# Part13_Power.net
KiCad netlist of a schematic drawn in Altium Designer
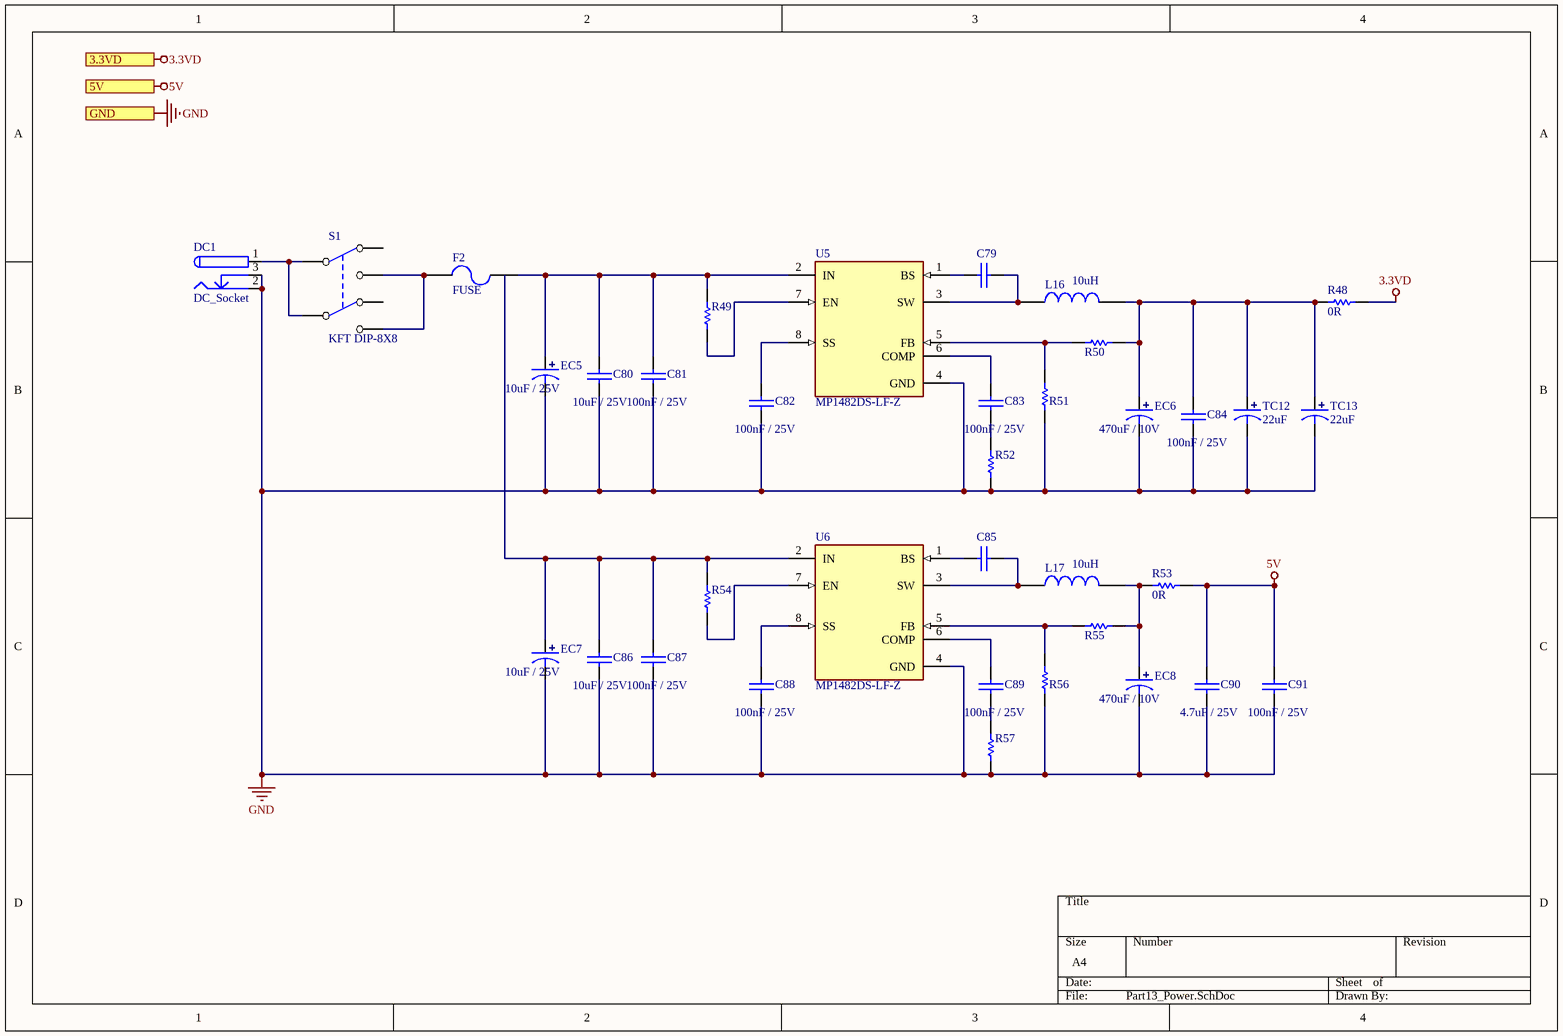
[diagram p0: Part13_Power.SchDoc]

(export (version "E")
  (design (tool "Eeschema 10.0.6"))
  (components
    (comp (ref "C79")
      (value "10nF / 25V")
      (footprint "0603C")
      (description "无极性电容")
      (libsource (lib "电容") (part "CAP"))
    )
    (comp (ref "C80")
      (value "10uF / 25V")
      (footprint "0603C")
      (description "无极性电容")
      (libsource (lib "电容") (part "CAP"))
    )
    (comp (ref "C81")
      (value "100nF / 25V")
      (footprint "0603C")
      (description "无极性电容")
      (libsource (lib "电容") (part "CAP"))
    )
    (comp (ref "C82")
      (value "100nF / 25V")
      (footprint "0603C")
      (description "无极性电容")
      (libsource (lib "电容") (part "CAP"))
    )
    (comp (ref "C83")
      (value "100nF / 25V")
      (footprint "0603C")
      (description "无极性电容")
      (libsource (lib "电容") (part "CAP"))
    )
    (comp (ref "C84")
      (value "100nF / 25V")
      (footprint "0603C")
      (description "无极性电容")
      (libsource (lib "电容") (part "CAP"))
    )
    (comp (ref "C85")
      (value "10nF / 25V")
      (footprint "0603C")
      (description "无极性电容")
      (libsource (lib "电容") (part "CAP"))
    )
    (comp (ref "C86")
      (value "10uF / 25V")
      (footprint "0603C")
      (description "无极性电容")
      (libsource (lib "电容") (part "CAP"))
    )
    (comp (ref "C87")
      (value "100nF / 25V")
      (footprint "0603C")
      (description "无极性电容")
      (libsource (lib "电容") (part "CAP"))
    )
    (comp (ref "C88")
      (value "100nF / 25V")
      (footprint "0603C")
      (description "无极性电容")
      (libsource (lib "电容") (part "CAP"))
    )
    (comp (ref "C89")
      (value "100nF / 25V")
      (footprint "0603C")
      (description "无极性电容")
      (libsource (lib "电容") (part "CAP"))
    )
    (comp (ref "C90")
      (value "4.7uF / 25V")
      (footprint "0603C")
      (description "无极性电容")
      (libsource (lib "电容") (part "CAP"))
    )
    (comp (ref "C91")
      (value "100nF / 25V")
      (footprint "0603C")
      (description "无极性电容")
      (libsource (lib "电容") (part "CAP"))
    )
    (comp (ref "DC1") (value "DC_Socket") (footprint "DC-005") (libsource (lib "电源插座") (part "DC_Socket")))
    (comp (ref "EC5")
      (value "10uF / 25V")
      (footprint "SMD-EC4.0X4.3X5.4")
      (description "贴片电解电容")
      (libsource (lib "电容") (part "SMD_ECAP"))
    )
    (comp (ref "EC6")
      (value "470uF / 10V")
      (footprint "SMD-EC6.3X6.3X10")
      (description "贴片电解电容")
      (libsource (lib "电容") (part "SMD_ECAP"))
    )
    (comp (ref "EC7")
      (value "10uF / 25V")
      (footprint "SMD-EC4.0X4.3X5.4")
      (description "贴片电解电容")
      (libsource (lib "电容") (part "SMD_ECAP"))
    )
    (comp (ref "EC8")
      (value "470uF / 10V")
      (footprint "SMD-EC6.3X6.3X10")
      (description "贴片电解电容")
      (libsource (lib "电容") (part "SMD_ECAP"))
    )
    (comp (ref "F2") (value "FUSE") (footprint "FUSE-1210") (libsource (lib "保险丝") (part "FUSE")))
    (comp (ref "L16")
      (value "10uH")
      (footprint "CD42")
      (description "INDUCTOR")
      (libsource (lib "电感") (part "INDUCTOR"))
    )
    (comp (ref "L17")
      (value "10uH")
      (footprint "CD42")
      (description "INDUCTOR")
      (libsource (lib "电感") (part "INDUCTOR"))
    )
    (comp (ref "R48") (value "0R") (footprint "0603R") (libsource (lib "电阻") (part "RES")))
    (comp (ref "R49") (value "30K") (footprint "0402R") (libsource (lib "电阻") (part "RES")))
    (comp (ref "R50") (value "26.1k / 1%") (footprint "0402R") (libsource (lib "电阻") (part "RES")))
    (comp (ref "R51") (value "10K / 1%") (footprint "0402R") (libsource (lib "电阻") (part "RES")))
    (comp (ref "R52") (value "5.6k") (footprint "0402R") (libsource (lib "电阻") (part "RES")))
    (comp (ref "R53") (value "0R") (footprint "0603R") (libsource (lib "电阻") (part "RES")))
    (comp (ref "R54") (value "30K") (footprint "0402R") (libsource (lib "电阻") (part "RES")))
    (comp (ref "R55") (value "26.1k / 1%") (footprint "0402R") (libsource (lib "电阻") (part "RES")))
    (comp (ref "R56") (value "10K / 1%") (footprint "0402R") (libsource (lib "电阻") (part "RES")))
    (comp (ref "R57") (value "5.6k") (footprint "0402R") (libsource (lib "电阻") (part "RES")))
    (comp (ref "S1")
      (value "KFT DIP-8X8")
      (footprint "KFT DIP-8X8")
      (libsource (lib "电源开关") (part "KFT DIP-8X8"))
    )
    (comp (ref "TC12")
      (value "22uF")
      (footprint "TAJ-A/3216")
      (description "钽电容")
      (libsource (lib "电容") (part "TCAP"))
    )
    (comp (ref "TC13")
      (value "22uF")
      (footprint "TAJ-A/3216")
      (description "钽电容")
      (libsource (lib "电容") (part "TCAP"))
    )
    (comp (ref "U5")
      (value "MP1482DS-LF-Z")
      (footprint "FP-MP1482DS-LF-Z-MFG")
      (description "IC REG BUCK ADJUSTABLE 2A 8SOIC")
      (fields
        (field (name "MANUFACTURER") "Monolithic Power Systems")
        (field (name "OCTOPART") "https://octopart.com/mp1482ds-lf-z-monolithic+power+systems-17392490")
      )
      (libsource (lib "Altium Content Vault") (part "ebfa2809f2b7d2844d3c4bd6b7ab285"))
    )
    (comp (ref "U6")
      (value "MP1482DS-LF-Z")
      (footprint "FP-MP1482DS-LF-Z-MFG")
      (description "IC REG BUCK ADJUSTABLE 2A 8SOIC")
      (fields
        (field (name "MANUFACTURER") "Monolithic Power Systems")
        (field (name "OCTOPART") "https://octopart.com/mp1482ds-lf-z-monolithic+power+systems-17392490")
      )
      (libsource (lib "Altium Content Vault") (part "ebfa2809f2b7d2844d3c4bd6b7ab285"))
    )
  )
  (nets
    (net (code "1") (name "3.3VD") (class "Default")
      (node (ref "R48") (pin "2") (pinfunction "2_2") (pintype "passive"))
    )
    (net (code "2") (name "5V") (class "Default")
      (node (ref "C90") (pin "2") (pinfunction "2_2") (pintype "passive"))
      (node (ref "C91") (pin "2") (pinfunction "2_2") (pintype "passive"))
      (node (ref "R53") (pin "2") (pinfunction "2_2") (pintype "passive"))
    )
    (net (code "3") (name "GND") (class "Default")
      (node (ref "C80") (pin "1") (pinfunction "1_1") (pintype "passive"))
      (node (ref "C81") (pin "1") (pinfunction "1_1") (pintype "passive"))
      (node (ref "C82") (pin "1") (pinfunction "1_1") (pintype "passive"))
      (node (ref "C84") (pin "1") (pinfunction "1_1") (pintype "passive"))
      (node (ref "C86") (pin "1") (pinfunction "1_1") (pintype "passive"))
      (node (ref "C87") (pin "1") (pinfunction "1_1") (pintype "passive"))
      (node (ref "C88") (pin "1") (pinfunction "1_1") (pintype "passive"))
      (node (ref "C90") (pin "1") (pinfunction "1_1") (pintype "passive"))
      (node (ref "C91") (pin "1") (pinfunction "1_1") (pintype "passive"))
      (node (ref "DC1") (pin "2") (pinfunction "2_2") (pintype "power_in"))
      (node (ref "DC1") (pin "3") (pinfunction "3_3") (pintype "power_in"))
      (node (ref "EC5") (pin "2") (pinfunction "2_2") (pintype "passive"))
      (node (ref "EC6") (pin "2") (pinfunction "2_2") (pintype "passive"))
      (node (ref "EC7") (pin "2") (pinfunction "2_2") (pintype "passive"))
      (node (ref "EC8") (pin "2") (pinfunction "2_2") (pintype "passive"))
      (node (ref "R51") (pin "1") (pinfunction "1_1") (pintype "passive"))
      (node (ref "R52") (pin "2") (pinfunction "2_2") (pintype "passive"))
      (node (ref "R56") (pin "1") (pinfunction "1_1") (pintype "passive"))
      (node (ref "R57") (pin "2") (pinfunction "2_2") (pintype "passive"))
      (node (ref "TC12") (pin "2") (pinfunction "2_2") (pintype "passive"))
      (node (ref "TC13") (pin "2") (pinfunction "2_2") (pintype "passive"))
      (node (ref "U5") (pin "4") (pinfunction "GND_4") (pintype "power_in"))
      (node (ref "U6") (pin "4") (pinfunction "GND_4") (pintype "power_in"))
    )
    (net (code "4") (name "Net-(C83-Pad1)") (class "Default")
      (node (ref "C83") (pin "1") (pinfunction "1_1") (pintype "passive"))
      (node (ref "R52") (pin "1") (pinfunction "1_1") (pintype "passive"))
    )
    (net (code "5") (name "Net-(C84-Pad2)") (class "Default")
      (node (ref "C84") (pin "2") (pinfunction "2_2") (pintype "passive"))
      (node (ref "EC6") (pin "1") (pinfunction "1_1") (pintype "passive"))
      (node (ref "L16") (pin "2") (pinfunction "2_2") (pintype "passive"))
      (node (ref "R48") (pin "1") (pinfunction "1_1") (pintype "passive"))
      (node (ref "R50") (pin "2") (pinfunction "2_2") (pintype "passive"))
      (node (ref "TC12") (pin "1") (pinfunction "1_1") (pintype "passive"))
      (node (ref "TC13") (pin "1") (pinfunction "1_1") (pintype "passive"))
    )
    (net (code "6") (name "Net-(C89-Pad1)") (class "Default")
      (node (ref "C89") (pin "1") (pinfunction "1_1") (pintype "passive"))
      (node (ref "R57") (pin "1") (pinfunction "1_1") (pintype "passive"))
    )
    (net (code "7") (name "Net-(DC1-Pad1)") (class "Default")
      (node (ref "DC1") (pin "1") (pinfunction "1_1") (pintype "power_in"))
      (node (ref "S1") (pin "2") (pinfunction "2_2") (pintype "passive"))
      (node (ref "S1") (pin "5") (pinfunction "5_5") (pintype "passive"))
    )
    (net (code "8") (name "Net-(EC8-Pad1)") (class "Default")
      (node (ref "EC8") (pin "1") (pinfunction "1_1") (pintype "passive"))
      (node (ref "L17") (pin "2") (pinfunction "2_2") (pintype "passive"))
      (node (ref "R53") (pin "1") (pinfunction "1_1") (pintype "passive"))
      (node (ref "R55") (pin "2") (pinfunction "2_2") (pintype "passive"))
    )
    (net (code "9") (name "Net-(F2-Pad1)") (class "Default")
      (node (ref "F2") (pin "1") (pinfunction "1_1") (pintype "passive"))
      (node (ref "S1") (pin "1") (pinfunction "1_1") (pintype "passive"))
      (node (ref "S1") (pin "6") (pinfunction "6_6") (pintype "passive"))
    )
    (net (code "10") (name "Net-(U5-BS)") (class "Default")
      (node (ref "C79") (pin "2") (pinfunction "2_2") (pintype "passive"))
      (node (ref "U5") (pin "1") (pinfunction "BS_1") (pintype "input"))
    )
    (net (code "11") (name "Net-(U5-COMP)") (class "Default")
      (node (ref "C83") (pin "2") (pinfunction "2_2") (pintype "passive"))
      (node (ref "U5") (pin "6") (pinfunction "COMP_6") (pintype "passive"))
    )
    (net (code "12") (name "Net-(U5-EN)") (class "Default")
      (node (ref "R49") (pin "2") (pinfunction "2_2") (pintype "passive"))
      (node (ref "U5") (pin "7") (pinfunction "EN_7") (pintype "input"))
    )
    (net (code "13") (name "Net-(U5-FB)") (class "Default")
      (node (ref "R50") (pin "1") (pinfunction "1_1") (pintype "passive"))
      (node (ref "R51") (pin "2") (pinfunction "2_2") (pintype "passive"))
      (node (ref "U5") (pin "5") (pinfunction "FB_5") (pintype "input"))
    )
    (net (code "14") (name "Net-(U5-IN)") (class "Default")
      (node (ref "C80") (pin "2") (pinfunction "2_2") (pintype "passive"))
      (node (ref "C81") (pin "2") (pinfunction "2_2") (pintype "passive"))
      (node (ref "EC5") (pin "1") (pinfunction "1_1") (pintype "passive"))
      (node (ref "F2") (pin "2") (pinfunction "2_2") (pintype "passive"))
      (node (ref "R49") (pin "1") (pinfunction "1_1") (pintype "passive"))
      (node (ref "U5") (pin "2") (pinfunction "IN_2") (pintype "power_in"))
    )
    (net (code "15") (name "Net-(U5-SS)") (class "Default")
      (node (ref "C82") (pin "2") (pinfunction "2_2") (pintype "passive"))
      (node (ref "U5") (pin "8") (pinfunction "SS_8") (pintype "input"))
    )
    (net (code "16") (name "Net-(U5-SW)") (class "Default")
      (node (ref "C79") (pin "1") (pinfunction "1_1") (pintype "passive"))
      (node (ref "L16") (pin "1") (pinfunction "1_1") (pintype "passive"))
      (node (ref "U5") (pin "3") (pinfunction "SW_3") (pintype "power_in"))
    )
    (net (code "17") (name "Net-(U6-BS)") (class "Default")
      (node (ref "C85") (pin "2") (pinfunction "2_2") (pintype "passive"))
      (node (ref "U6") (pin "1") (pinfunction "BS_1") (pintype "input"))
    )
    (net (code "18") (name "Net-(U6-COMP)") (class "Default")
      (node (ref "C89") (pin "2") (pinfunction "2_2") (pintype "passive"))
      (node (ref "U6") (pin "6") (pinfunction "COMP_6") (pintype "passive"))
    )
    (net (code "19") (name "Net-(U6-EN)") (class "Default")
      (node (ref "R54") (pin "2") (pinfunction "2_2") (pintype "passive"))
      (node (ref "U6") (pin "7") (pinfunction "EN_7") (pintype "input"))
    )
    (net (code "20") (name "Net-(U6-FB)") (class "Default")
      (node (ref "R55") (pin "1") (pinfunction "1_1") (pintype "passive"))
      (node (ref "R56") (pin "2") (pinfunction "2_2") (pintype "passive"))
      (node (ref "U6") (pin "5") (pinfunction "FB_5") (pintype "input"))
    )
    (net (code "21") (name "Net-(U6-IN)") (class "Default")
      (node (ref "C86") (pin "2") (pinfunction "2_2") (pintype "passive"))
      (node (ref "C87") (pin "2") (pinfunction "2_2") (pintype "passive"))
      (node (ref "EC7") (pin "1") (pinfunction "1_1") (pintype "passive"))
      (node (ref "R54") (pin "1") (pinfunction "1_1") (pintype "passive"))
      (node (ref "U6") (pin "2") (pinfunction "IN_2") (pintype "power_in"))
    )
    (net (code "22") (name "Net-(U6-SS)") (class "Default")
      (node (ref "C88") (pin "2") (pinfunction "2_2") (pintype "passive"))
      (node (ref "U6") (pin "8") (pinfunction "SS_8") (pintype "input"))
    )
    (net (code "23") (name "Net-(U6-SW)") (class "Default")
      (node (ref "C85") (pin "1") (pinfunction "1_1") (pintype "passive"))
      (node (ref "L17") (pin "1") (pinfunction "1_1") (pintype "passive"))
      (node (ref "U6") (pin "3") (pinfunction "SW_3") (pintype "power_in"))
    )
    (net (code "24") (name "unconnected-(S1-Pad3)") (class "Default")
      (node (ref "S1") (pin "3") (pinfunction "3_3") (pintype "passive"))
    )
    (net (code "25") (name "unconnected-(S1-Pad4)") (class "Default")
      (node (ref "S1") (pin "4") (pinfunction "4_4") (pintype "passive"))
    )
  )
)
